# Divider.net
KiCad netlist of a schematic drawn in Altium Designer
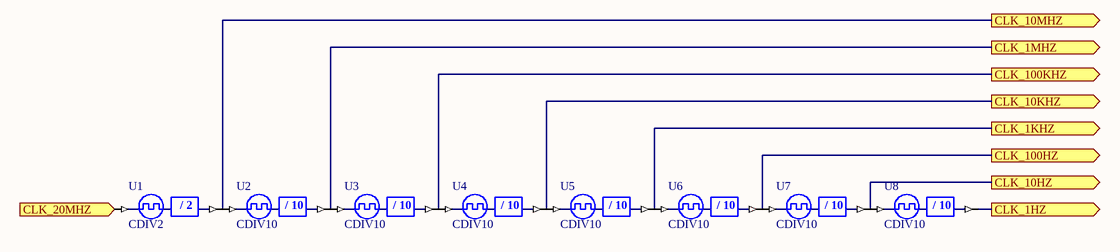
[diagram p0: Divider.schdoc]

(export (version "E")
  (design (tool "Eeschema 10.0.6"))
  (components
    (comp (ref "U1")
      (value "CDIV2")
      (description "Clock Divider by 2")
      (fields (field (name "PUBLISHER") "Altium Limited"))
      (libsource (lib "FPGA Generic") (part "CDIV2"))
    )
    (comp (ref "U2")
      (value "CDIV10")
      (description "Clock Divider by 10")
      (fields (field (name "PUBLISHER") "Altium Limited"))
      (libsource (lib "FPGA Generic") (part "CDIV10"))
    )
    (comp (ref "U3")
      (value "CDIV10")
      (description "Clock Divider by 10")
      (fields (field (name "PUBLISHER") "Altium Limited"))
      (libsource (lib "FPGA Generic") (part "CDIV10"))
    )
    (comp (ref "U4")
      (value "CDIV10")
      (description "Clock Divider by 10")
      (fields (field (name "PUBLISHER") "Altium Limited"))
      (libsource (lib "FPGA Generic") (part "CDIV10"))
    )
    (comp (ref "U5")
      (value "CDIV10")
      (description "Clock Divider by 10")
      (fields (field (name "PUBLISHER") "Altium Limited"))
      (libsource (lib "FPGA Generic") (part "CDIV10"))
    )
    (comp (ref "U6")
      (value "CDIV10")
      (description "Clock Divider by 10")
      (fields (field (name "PUBLISHER") "Altium Limited"))
      (libsource (lib "FPGA Generic") (part "CDIV10"))
    )
    (comp (ref "U7")
      (value "CDIV10")
      (description "Clock Divider by 10")
      (fields (field (name "PUBLISHER") "Altium Limited"))
      (libsource (lib "FPGA Generic") (part "CDIV10"))
    )
    (comp (ref "U8")
      (value "CDIV10")
      (description "Clock Divider by 10")
      (fields (field (name "PUBLISHER") "Altium Limited"))
      (libsource (lib "FPGA Generic") (part "CDIV10"))
    )
  )
  (nets
    (net (code "1") (name "/CLK_1HZ") (class "Default")
      (node (ref "U8") (pin "CLKDV") (pinfunction "CLKDV_CLKDV") (pintype "output"))
    )
    (net (code "2") (name "/CLK_1KHZ") (class "Default")
      (node (ref "U5") (pin "CLKDV") (pinfunction "CLKDV_CLKDV") (pintype "output"))
      (node (ref "U6") (pin "CLKIN") (pinfunction "CLKIN_CLKIN") (pintype "input"))
    )
    (net (code "3") (name "/CLK_1MHZ") (class "Default")
      (node (ref "U2") (pin "CLKDV") (pinfunction "CLKDV_CLKDV") (pintype "output"))
      (node (ref "U3") (pin "CLKIN") (pinfunction "CLKIN_CLKIN") (pintype "input"))
    )
    (net (code "4") (name "/CLK_10HZ") (class "Default")
      (node (ref "U7") (pin "CLKDV") (pinfunction "CLKDV_CLKDV") (pintype "output"))
      (node (ref "U8") (pin "CLKIN") (pinfunction "CLKIN_CLKIN") (pintype "input"))
    )
    (net (code "5") (name "/CLK_10KHZ") (class "Default")
      (node (ref "U4") (pin "CLKDV") (pinfunction "CLKDV_CLKDV") (pintype "output"))
      (node (ref "U5") (pin "CLKIN") (pinfunction "CLKIN_CLKIN") (pintype "input"))
    )
    (net (code "6") (name "/CLK_10MHZ") (class "Default")
      (node (ref "U1") (pin "CLKDV") (pinfunction "CLKDV_CLKDV") (pintype "output"))
      (node (ref "U2") (pin "CLKIN") (pinfunction "CLKIN_CLKIN") (pintype "input"))
    )
    (net (code "7") (name "/CLK_20MHZ") (class "Default")
      (node (ref "U1") (pin "CLKIN") (pinfunction "CLKIN_CLKIN") (pintype "input"))
    )
    (net (code "8") (name "/CLK_100HZ") (class "Default")
      (node (ref "U6") (pin "CLKDV") (pinfunction "CLKDV_CLKDV") (pintype "output"))
      (node (ref "U7") (pin "CLKIN") (pinfunction "CLKIN_CLKIN") (pintype "input"))
    )
    (net (code "9") (name "/CLK_100KHZ") (class "Default")
      (node (ref "U3") (pin "CLKDV") (pinfunction "CLKDV_CLKDV") (pintype "output"))
      (node (ref "U4") (pin "CLKIN") (pinfunction "CLKIN_CLKIN") (pintype "input"))
    )
  )
)
